# Sensors.net
KiCad netlist of a schematic drawn in Altium Designer
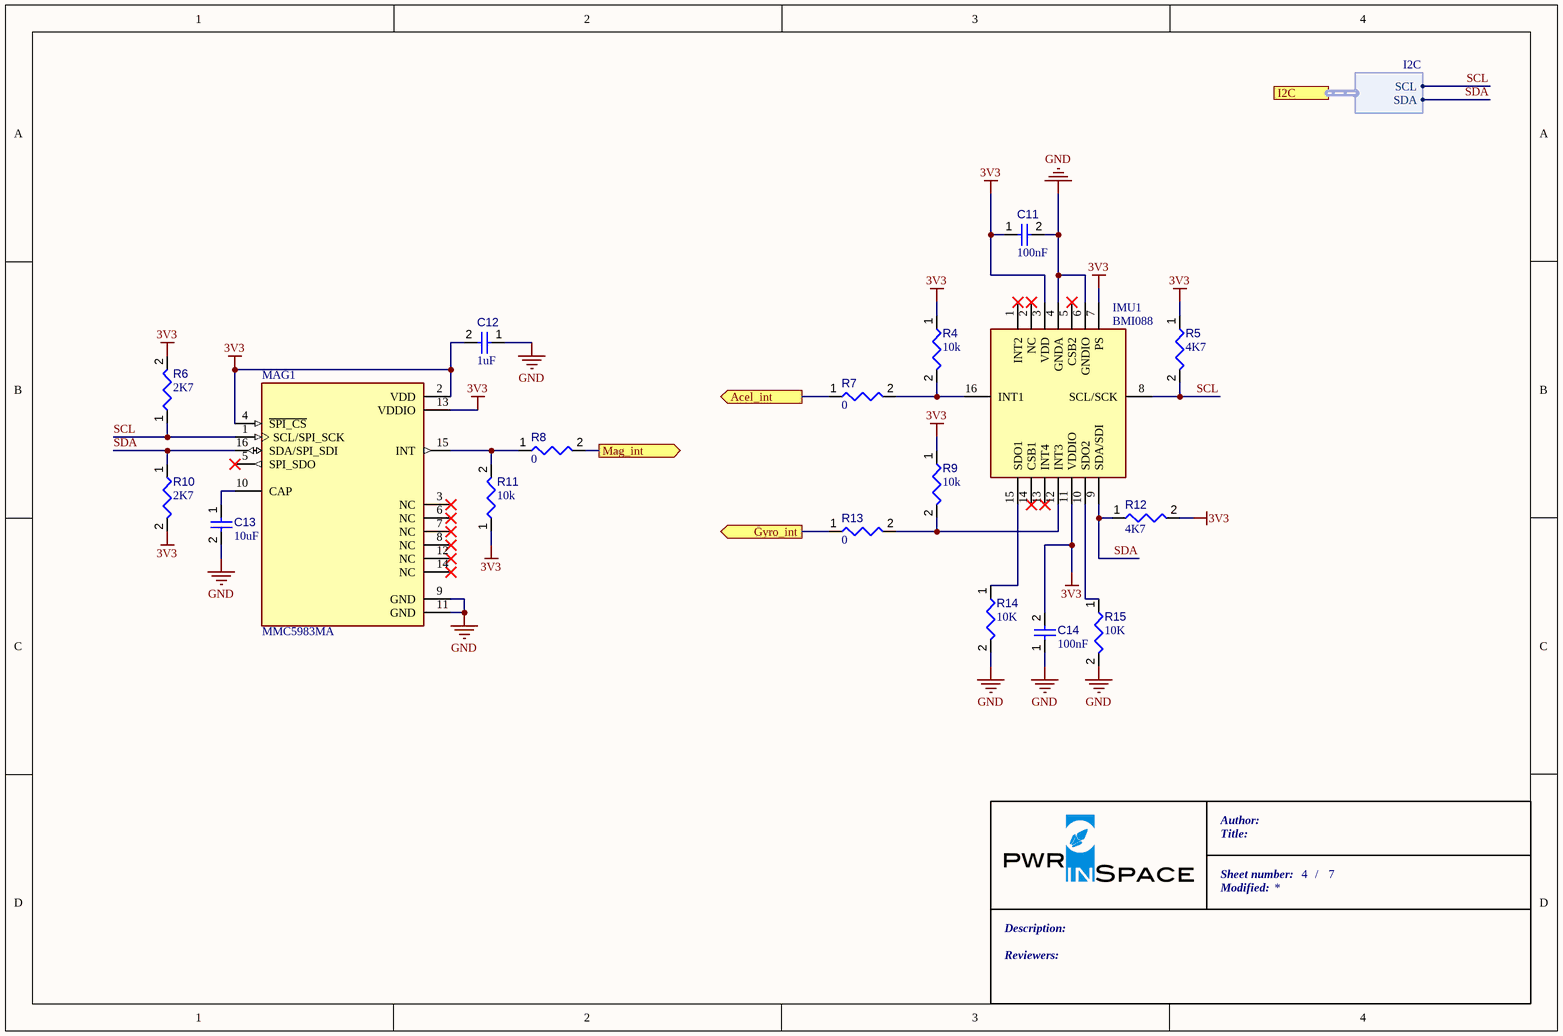
[diagram p0: Sensors.SchDoc]

(export (version "E")
  (design (tool "Eeschema 10.0.6"))
  (components
    (comp (ref "C11")
      (value "100nF")
      (footprint "CAPC0805(2012)145_L")
      (description "Chip Capacitor, 100µF +/-20%, 6.3V, 0805, Thickness 1.45 mm")
      (fields (field (name "TOLERANCE") "10%") (field (name "Comment") "Capacitor 100µF +/-20% 6.3V 0805"))
      (libsource (lib "PWr in Space team") (part "CAP-NP-2"))
    )
    (comp (ref "C12")
      (value "1uF")
      (footprint "CAPC0805(2012)145_L")
      (description "Chip Capacitor, 100µF +/-20%, 6.3V, 0805, Thickness 1.45 mm")
      (fields (field (name "TOLERANCE") "10%") (field (name "Comment") "Capacitor 100µF +/-20% 6.3V 0805"))
      (libsource (lib "PWr in Space team") (part "CAP-NP-2"))
    )
    (comp (ref "C13")
      (value "10uF")
      (footprint "CAPC0805(2012)145_L")
      (description "Chip Capacitor, 100µF +/-20%, 6.3V, 0805, Thickness 1.45 mm")
      (fields (field (name "TOLERANCE") "10%") (field (name "Comment") "Capacitor 100µF +/-20% 6.3V 0805"))
      (libsource (lib "PWr in Space team") (part "CAP-NP-2"))
    )
    (comp (ref "C14")
      (value "100nF")
      (footprint "CAPC0805(2012)145_L")
      (description "Chip Capacitor, 100µF +/-20%, 6.3V, 0805, Thickness 1.45 mm")
      (fields (field (name "TOLERANCE") "10%") (field (name "Comment") "Capacitor 100µF +/-20% 6.3V 0805"))
      (libsource (lib "PWr in Space team") (part "CAP-NP-2"))
    )
    (comp (ref "IMU1")
      (value "BMI088")
      (footprint "BMI088")
      (description "Integrated Circuit")
      (fields (field (name "MOUSER PART NUMBER") "262-BMI088"))
      (libsource (lib "PWr in Space team") (part "BMI088"))
    )
    (comp (ref "MAG1")
      (value "MMC5983MA")
      (footprint "PQFN50P300X300X100-16N")
      (description "MMC5983 series Magnetic, Magnetometer Sensor Evaluation Board")
      (fields (field (name "MF") "{'manufacturer': u'Memsic Inc.'}"))
      (libsource (lib "PWr in Space team") (part "MMC5983MA"))
    )
    (comp (ref "R4")
      (value "10k")
      (footprint "RESC0805(2012)_L")
      (description "Chip Resistor, 4,7 Ohms, +/-5 %, 125 mW, -55 to 155 degC, 0805")
      (fields (field (name "TOLERANCE") "5%") (field (name "POWER") "125mW"))
      (libsource (lib "PWr in Space team") (part "RES-2"))
    )
    (comp (ref "R5")
      (value "4K7")
      (footprint "RESC0805(2012)_L")
      (description "Chip Resistor, 4,7 Ohms, +/-5 %, 125 mW, -55 to 155 degC, 0805")
      (fields (field (name "TOLERANCE") "5%") (field (name "POWER") "125mW"))
      (libsource (lib "PWr in Space team") (part "RES-2"))
    )
    (comp (ref "R6")
      (value "2K7")
      (footprint "RESC0805(2012)_L")
      (description "Chip Resistor, 4,7 Ohms, +/-5 %, 125 mW, -55 to 155 degC, 0805")
      (fields (field (name "TOLERANCE") "5%") (field (name "POWER") "125mW"))
      (libsource (lib "PWr in Space team") (part "RES-2"))
    )
    (comp (ref "R7")
      (value "0")
      (footprint "RESC0805(2012)_L")
      (description "Chip Resistor, 4,7 Ohms, +/-5 %, 125 mW, -55 to 155 degC, 0805")
      (fields (field (name "TOLERANCE") "5%") (field (name "POWER") "125mW"))
      (libsource (lib "PWr in Space team") (part "RES-2"))
    )
    (comp (ref "R8")
      (value "0")
      (footprint "RESC0805(2012)_L")
      (description "Chip Resistor, 4,7 Ohms, +/-5 %, 125 mW, -55 to 155 degC, 0805")
      (fields (field (name "TOLERANCE") "5%") (field (name "POWER") "125mW"))
      (libsource (lib "PWr in Space team") (part "RES-2"))
    )
    (comp (ref "R9")
      (value "10k")
      (footprint "RESC0805(2012)_L")
      (description "Chip Resistor, 4,7 Ohms, +/-5 %, 125 mW, -55 to 155 degC, 0805")
      (fields (field (name "TOLERANCE") "5%") (field (name "POWER") "125mW"))
      (libsource (lib "PWr in Space team") (part "RES-2"))
    )
    (comp (ref "R10")
      (value "2K7")
      (footprint "RESC0805(2012)_L")
      (description "Chip Resistor, 4,7 Ohms, +/-5 %, 125 mW, -55 to 155 degC, 0805")
      (fields (field (name "TOLERANCE") "5%") (field (name "POWER") "125mW"))
      (libsource (lib "PWr in Space team") (part "RES-2"))
    )
    (comp (ref "R11")
      (value "10k")
      (footprint "RESC0805(2012)_L")
      (description "Chip Resistor, 4,7 Ohms, +/-5 %, 125 mW, -55 to 155 degC, 0805")
      (fields (field (name "TOLERANCE") "5%") (field (name "POWER") "125mW"))
      (libsource (lib "PWr in Space team") (part "RES-2"))
    )
    (comp (ref "R12")
      (value "4K7")
      (footprint "RESC0805(2012)_L")
      (description "Chip Resistor, 4,7 Ohms, +/-5 %, 125 mW, -55 to 155 degC, 0805")
      (fields (field (name "TOLERANCE") "5%") (field (name "POWER") "125mW"))
      (libsource (lib "PWr in Space team") (part "RES-2"))
    )
    (comp (ref "R13")
      (value "0")
      (footprint "RESC0805(2012)_L")
      (description "Chip Resistor, 4,7 Ohms, +/-5 %, 125 mW, -55 to 155 degC, 0805")
      (fields (field (name "TOLERANCE") "5%") (field (name "POWER") "125mW"))
      (libsource (lib "PWr in Space team") (part "RES-2"))
    )
    (comp (ref "R14")
      (value "10K")
      (footprint "RESC0805(2012)_L")
      (description "Chip Resistor, 4,7 Ohms, +/-5 %, 125 mW, -55 to 155 degC, 0805")
      (fields (field (name "TOLERANCE") "5%") (field (name "POWER") "125mW"))
      (libsource (lib "PWr in Space team") (part "RES-2"))
    )
    (comp (ref "R15")
      (value "10K")
      (footprint "RESC0805(2012)_L")
      (description "Chip Resistor, 4,7 Ohms, +/-5 %, 125 mW, -55 to 155 degC, 0805")
      (fields (field (name "TOLERANCE") "5%") (field (name "POWER") "125mW"))
      (libsource (lib "PWr in Space team") (part "RES-2"))
    )
  )
  (nets
    (net (code "2") (name "/Acel_int") (class "Default")
      (node (ref "R7") (pin "1") (pinfunction "1_1") (pintype "passive"))
    )
    (net (code "3") (name "/Gyro_int") (class "Default")
      (node (ref "R13") (pin "1") (pinfunction "1_1") (pintype "passive"))
    )
    (net (code "4") (name "/Mag_int") (class "Default")
      (node (ref "R8") (pin "2") (pinfunction "2_2") (pintype "passive"))
    )
    (net (code "5") (name "/SCL") (class "Default")
      (node (ref "IMU1") (pin "8") (pinfunction "SCL/SCK_8") (pintype "passive"))
      (node (ref "MAG1") (pin "1") (pinfunction "SCL/SPI_SCK_1") (pintype "input"))
      (node (ref "R5") (pin "2") (pinfunction "2_2") (pintype "passive"))
      (node (ref "R6") (pin "1") (pinfunction "1_1") (pintype "passive"))
    )
    (net (code "6") (name "/SDA") (class "Default")
      (node (ref "IMU1") (pin "9") (pinfunction "SDA/SDI_9") (pintype "passive"))
      (node (ref "MAG1") (pin "16") (pinfunction "SDA/SPI_SDI_16") (pintype "bidirectional"))
      (node (ref "R10") (pin "1") (pinfunction "1_1") (pintype "passive"))
      (node (ref "R12") (pin "1") (pinfunction "1_1") (pintype "passive"))
    )
    (net (code "8") (name "3V3") (class "Default")
      (node (ref "C11") (pin "1") (pinfunction "1_1") (pintype "passive"))
      (node (ref "C12") (pin "2") (pinfunction "2_2") (pintype "passive"))
      (node (ref "C14") (pin "2") (pinfunction "2_2") (pintype "passive"))
      (node (ref "IMU1") (pin "11") (pinfunction "VDDIO_11") (pintype "passive"))
      (node (ref "IMU1") (pin "3") (pinfunction "VDD_3") (pintype "passive"))
      (node (ref "IMU1") (pin "7") (pinfunction "PS_7") (pintype "passive"))
      (node (ref "MAG1") (pin "13") (pinfunction "VDDIO_13") (pintype "power_in"))
      (node (ref "MAG1") (pin "2") (pinfunction "VDD_2") (pintype "power_in"))
      (node (ref "MAG1") (pin "4") (pinfunction "~{SPI_CS}_4") (pintype "input"))
      (node (ref "R10") (pin "2") (pinfunction "2_2") (pintype "passive"))
      (node (ref "R11") (pin "1") (pinfunction "1_1") (pintype "passive"))
      (node (ref "R12") (pin "2") (pinfunction "2_2") (pintype "passive"))
      (node (ref "R4") (pin "1") (pinfunction "1_1") (pintype "passive"))
      (node (ref "R5") (pin "1") (pinfunction "1_1") (pintype "passive"))
      (node (ref "R6") (pin "2") (pinfunction "2_2") (pintype "passive"))
      (node (ref "R9") (pin "1") (pinfunction "1_1") (pintype "passive"))
    )
    (net (code "9") (name "GND") (class "Default")
      (node (ref "C11") (pin "2") (pinfunction "2_2") (pintype "passive"))
      (node (ref "C12") (pin "1") (pinfunction "1_1") (pintype "passive"))
      (node (ref "C13") (pin "2") (pinfunction "2_2") (pintype "passive"))
      (node (ref "C14") (pin "1") (pinfunction "1_1") (pintype "passive"))
      (node (ref "IMU1") (pin "4") (pinfunction "GNDA_4") (pintype "passive"))
      (node (ref "IMU1") (pin "6") (pinfunction "GNDIO_6") (pintype "passive"))
      (node (ref "MAG1") (pin "11") (pinfunction "GND_11") (pintype "power_in"))
      (node (ref "MAG1") (pin "9") (pinfunction "GND_9") (pintype "power_in"))
      (node (ref "R14") (pin "2") (pinfunction "2_2") (pintype "passive"))
      (node (ref "R15") (pin "2") (pinfunction "2_2") (pintype "passive"))
    )
    (net (code "10") (name "Net-(IMU1-INT1)") (class "Default")
      (node (ref "IMU1") (pin "16") (pinfunction "INT1_16") (pintype "passive"))
      (node (ref "R4") (pin "2") (pinfunction "2_2") (pintype "passive"))
      (node (ref "R7") (pin "2") (pinfunction "2_2") (pintype "passive"))
    )
    (net (code "11") (name "Net-(IMU1-INT3)") (class "Default")
      (node (ref "IMU1") (pin "12") (pinfunction "INT3_12") (pintype "passive"))
      (node (ref "R13") (pin "2") (pinfunction "2_2") (pintype "passive"))
      (node (ref "R9") (pin "2") (pinfunction "2_2") (pintype "passive"))
    )
    (net (code "12") (name "Net-(IMU1-SDO1)") (class "Default")
      (node (ref "IMU1") (pin "15") (pinfunction "SDO1_15") (pintype "passive"))
      (node (ref "R14") (pin "1") (pinfunction "1_1") (pintype "passive"))
    )
    (net (code "13") (name "Net-(IMU1-SDO2)") (class "Default")
      (node (ref "IMU1") (pin "10") (pinfunction "SDO2_10") (pintype "passive"))
      (node (ref "R15") (pin "1") (pinfunction "1_1") (pintype "passive"))
    )
    (net (code "14") (name "Net-(MAG1-CAP)") (class "Default")
      (node (ref "C13") (pin "1") (pinfunction "1_1") (pintype "passive"))
      (node (ref "MAG1") (pin "10") (pinfunction "CAP_10") (pintype "passive"))
    )
    (net (code "15") (name "Net-(MAG1-INT)") (class "Default")
      (node (ref "MAG1") (pin "15") (pinfunction "INT_15") (pintype "output"))
      (node (ref "R11") (pin "2") (pinfunction "2_2") (pintype "passive"))
      (node (ref "R8") (pin "1") (pinfunction "1_1") (pintype "passive"))
    )
    (net (code "16") (name "unconnected-(IMU1-CSB1-Pad14)") (class "Default")
      (node (ref "IMU1") (pin "14") (pinfunction "CSB1_14") (pintype "passive+no_connect"))
    )
    (net (code "17") (name "unconnected-(IMU1-CSB2-Pad5)") (class "Default")
      (node (ref "IMU1") (pin "5") (pinfunction "CSB2_5") (pintype "passive+no_connect"))
    )
    (net (code "18") (name "unconnected-(IMU1-INT2-Pad1)") (class "Default")
      (node (ref "IMU1") (pin "1") (pinfunction "INT2_1") (pintype "passive+no_connect"))
    )
    (net (code "19") (name "unconnected-(IMU1-INT4-Pad13)") (class "Default")
      (node (ref "IMU1") (pin "13") (pinfunction "INT4_13") (pintype "passive+no_connect"))
    )
    (net (code "20") (name "unconnected-(IMU1-NC-Pad2)") (class "Default")
      (node (ref "IMU1") (pin "2") (pinfunction "NC_2") (pintype "passive+no_connect"))
    )
    (net (code "21") (name "unconnected-(MAG1-NC-Pad3)") (class "Default")
      (node (ref "MAG1") (pin "3") (pinfunction "NC_3") (pintype "passive+no_connect"))
    )
    (net (code "22") (name "unconnected-(MAG1-NC-Pad6)") (class "Default")
      (node (ref "MAG1") (pin "6") (pinfunction "NC_6") (pintype "passive+no_connect"))
    )
    (net (code "23") (name "unconnected-(MAG1-NC-Pad7)") (class "Default")
      (node (ref "MAG1") (pin "7") (pinfunction "NC_7") (pintype "passive+no_connect"))
    )
    (net (code "24") (name "unconnected-(MAG1-NC-Pad8)") (class "Default")
      (node (ref "MAG1") (pin "8") (pinfunction "NC_8") (pintype "passive+no_connect"))
    )
    (net (code "25") (name "unconnected-(MAG1-NC-Pad12)") (class "Default")
      (node (ref "MAG1") (pin "12") (pinfunction "NC_12") (pintype "passive+no_connect"))
    )
    (net (code "26") (name "unconnected-(MAG1-NC-Pad14)") (class "Default")
      (node (ref "MAG1") (pin "14") (pinfunction "NC_14") (pintype "passive+no_connect"))
    )
    (net (code "27") (name "unconnected-(MAG1-SPI_SDO-Pad5)") (class "Default")
      (node (ref "MAG1") (pin "5") (pinfunction "SPI_SDO_5") (pintype "output+no_connect"))
    )
  )
)
